# TanveerMPPT_02_1.net
KiCad netlist of a schematic drawn in EAGLE
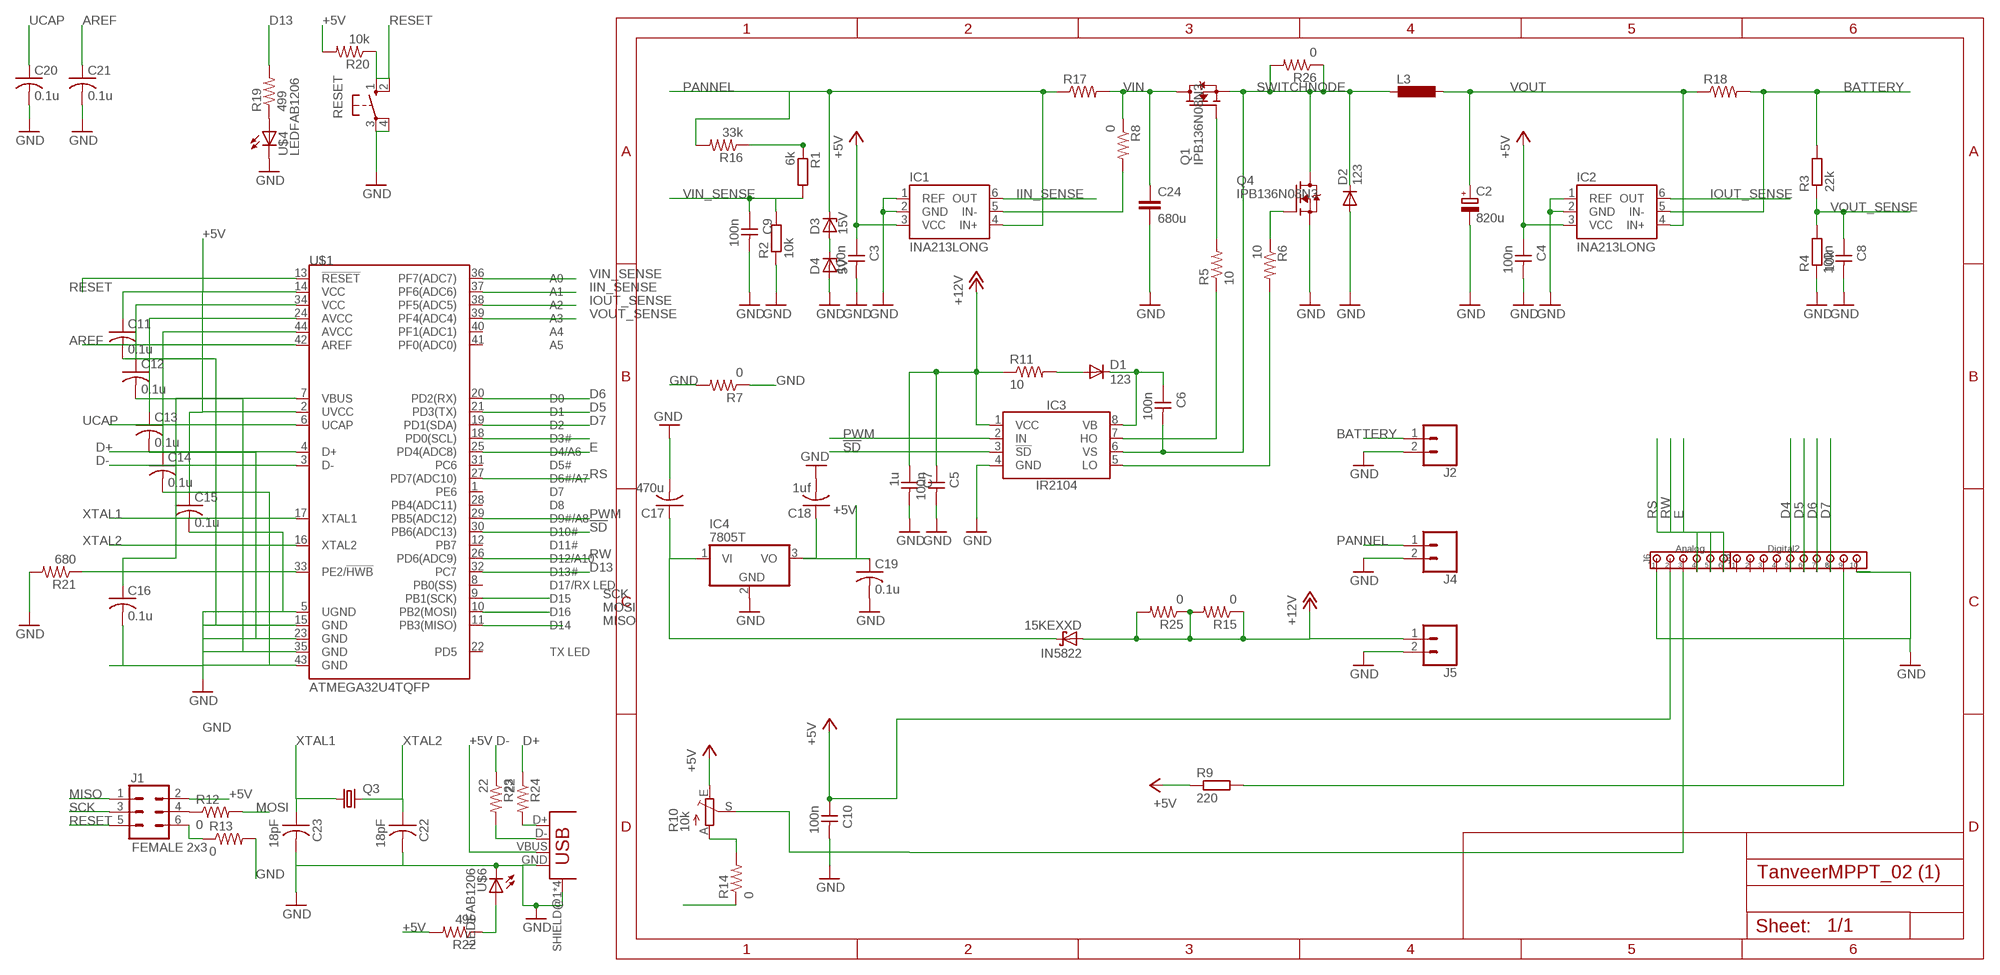
[diagram p0: schematic, sheet 1]

(export (version "E")
  (design (tool "Eeschema 10.0.6"))
  (components
    (comp (ref "C2")
      (value "820u")
      (footprint "eagle-import:10MM")
      (libsource (lib "eagle-import") (part "C_POLARIZED10MM"))
    )
    (comp (ref "C3")
      (value "100n")
      (footprint "eagle-import:C1206")
      (libsource (lib "eagle-import") (part "CAP-UNPOLARIZED"))
    )
    (comp (ref "C4")
      (value "100n")
      (footprint "eagle-import:C1206FAB")
      (libsource (lib "eagle-import") (part "CAP-UNPOLARIZEDFAB"))
    )
    (comp (ref "C5")
      (value "100n")
      (footprint "eagle-import:C1206FAB")
      (libsource (lib "eagle-import") (part "CAP-UNPOLARIZEDFAB"))
    )
    (comp (ref "C6")
      (value "100n")
      (footprint "eagle-import:C1206FAB")
      (libsource (lib "eagle-import") (part "CAP-UNPOLARIZEDFAB"))
    )
    (comp (ref "C7")
      (value "1u")
      (footprint "eagle-import:C1206FAB")
      (libsource (lib "eagle-import") (part "CAP-UNPOLARIZEDFAB"))
    )
    (comp (ref "C8")
      (value "100n")
      (footprint "eagle-import:C1206")
      (libsource (lib "eagle-import") (part "CAP-UNPOLARIZED"))
    )
    (comp (ref "C9")
      (value "100n")
      (footprint "eagle-import:C1206FAB")
      (libsource (lib "eagle-import") (part "CAP-UNPOLARIZEDFAB"))
    )
    (comp (ref "C10")
      (value "100n")
      (footprint "eagle-import:C1206FAB")
      (libsource (lib "eagle-import") (part "CAP-UNPOLARIZEDFAB"))
    )
    (comp (ref "C11")
      (value "0.1u")
      (footprint "eagle-import:C1206")
      (libsource (lib "eagle-import") (part "C-USC1206"))
    )
    (comp (ref "C12")
      (value "0.1u")
      (footprint "eagle-import:C1206")
      (libsource (lib "eagle-import") (part "C-USC1206"))
    )
    (comp (ref "C13")
      (value "0.1u")
      (footprint "eagle-import:C1206")
      (libsource (lib "eagle-import") (part "C-USC1206"))
    )
    (comp (ref "C14")
      (value "0.1u")
      (footprint "eagle-import:C1206")
      (libsource (lib "eagle-import") (part "C-USC1206"))
    )
    (comp (ref "C15")
      (value "0.1u")
      (footprint "eagle-import:C1206")
      (libsource (lib "eagle-import") (part "C-USC1206"))
    )
    (comp (ref "C16")
      (value "0.1u")
      (footprint "eagle-import:C1206")
      (libsource (lib "eagle-import") (part "C-USC1206"))
    )
    (comp (ref "C17")
      (value "470u")
      (footprint "eagle-import:C1206")
      (libsource (lib "eagle-import") (part "C-USC1206"))
    )
    (comp (ref "C18")
      (value "1uf")
      (footprint "eagle-import:C1206")
      (libsource (lib "eagle-import") (part "C-USC1206"))
    )
    (comp (ref "C19")
      (value "0.1u")
      (footprint "eagle-import:C1206")
      (libsource (lib "eagle-import") (part "C-USC1206"))
    )
    (comp (ref "C20")
      (value "0.1u")
      (footprint "eagle-import:C1206")
      (libsource (lib "eagle-import") (part "C-USC1206"))
    )
    (comp (ref "C21")
      (value "0.1u")
      (footprint "eagle-import:C1206")
      (libsource (lib "eagle-import") (part "C-USC1206"))
    )
    (comp (ref "C22")
      (value "18pF")
      (footprint "eagle-import:C1206FAB")
      (libsource (lib "eagle-import") (part "CAP-US1206FAB"))
    )
    (comp (ref "C23")
      (value "18pF")
      (footprint "eagle-import:C1206FAB")
      (libsource (lib "eagle-import") (part "CAP-US1206FAB"))
    )
    (comp (ref "C24")
      (value "680u")
      (footprint "eagle-import:CAP-PTH-10MM")
      (libsource (lib "eagle-import") (part "10NF-PTH-10MM-10000V-1-%"))
    )
    (comp (ref "D1")
      (value "123")
      (footprint "eagle-import:DO41-10")
      (libsource (lib "eagle-import") (part "1N4004"))
    )
    (comp (ref "D2")
      (value "123")
      (footprint "eagle-import:DO41-10")
      (libsource (lib "eagle-import") (part "1N4004"))
    )
    (comp (ref "D3")
      (value "15V")
      (footprint "eagle-import:DO41Z10")
      (libsource (lib "eagle-import") (part "ZENER-DIODEDO41Z10"))
    )
    (comp (ref "D4")
      (value "5V")
      (footprint "eagle-import:DO41Z10")
      (libsource (lib "eagle-import") (part "ZENER-DIODEDO41Z10"))
    )
    (comp (ref "IC1")
      (value "INA213LONG")
      (footprint "eagle-import:SC70-6_LONG")
      (libsource (lib "eagle-import") (part "INA21LONG3"))
    )
    (comp (ref "IC2")
      (value "INA213LONG")
      (footprint "eagle-import:SC70-6_LONG")
      (libsource (lib "eagle-import") (part "INA21LONG3"))
    )
    (comp (ref "IC3")
      (value "IR2104")
      (footprint "eagle-import:SOIC8")
      (libsource (lib "eagle-import") (part "IR2104"))
    )
    (comp (ref "IC4")
      (value "7805T")
      (footprint "eagle-import:TO220H")
      (libsource (lib "eagle-import") (part "78T05"))
    )
    (comp (ref "IN5822")
      (value "15KEXXD")
      (footprint "eagle-import:DO201T15")
      (libsource (lib "eagle-import") (part "15KEXXD"))
    )
    (comp (ref "J1")
      (value "FEMALE 2x3")
      (footprint "eagle-import:2X3")
      (libsource (lib "eagle-import") (part "CONN_03X2FEMALE"))
    )
    (comp (ref "J2")
      (value "CONN_02PTH4")
      (footprint "eagle-import:1X02_XTRA_BIG")
      (libsource (lib "eagle-import") (part "CONN_02PTH4"))
    )
    (comp (ref "J3")
      (value "Digital2")
      (footprint "eagle-import:100MIL_10X_ROUND")
      (libsource (lib "eagle-import") (part "100MIL_10X"))
    )
    (comp (ref "J4")
      (value "CONN_02PTH4")
      (footprint "eagle-import:1X02_XTRA_BIG")
      (libsource (lib "eagle-import") (part "CONN_02PTH4"))
    )
    (comp (ref "J5")
      (value "CONN_02PTH4")
      (footprint "eagle-import:1X02_XTRA_BIG")
      (libsource (lib "eagle-import") (part "CONN_02PTH4"))
    )
    (comp (ref "J6")
      (value "Analog")
      (footprint "eagle-import:100MIL_6X_ROUND")
      (libsource (lib "eagle-import") (part "100MIL_6X"))
    )
    (comp (ref "L3")
      (value "L-EUIR-4")
      (footprint "eagle-import:IR-4")
      (libsource (lib "eagle-import") (part "L-EUIR-4"))
    )
    (comp (ref "Q1")
      (value "IPB136N08N3")
      (footprint "eagle-import:TO263-3")
      (libsource (lib "eagle-import") (part "N-PWR-MOSFETTO263-3"))
    )
    (comp (ref "Q3")
      (value "CRYSTALTC26V")
      (footprint "eagle-import:TC26V")
      (libsource (lib "eagle-import") (part "CRYSTALTC26V"))
    )
    (comp (ref "Q4")
      (value "IPB136N08N3")
      (footprint "eagle-import:TO263-3")
      (libsource (lib "eagle-import") (part "N-PWR-MOSFETTO263-3"))
    )
    (comp (ref "R1")
      (value "6k")
      (footprint "eagle-import:M1206")
      (libsource (lib "eagle-import") (part "R-EU_M1206"))
    )
    (comp (ref "R2")
      (value "10k")
      (footprint "eagle-import:M1206")
      (libsource (lib "eagle-import") (part "R-EU_M1206"))
    )
    (comp (ref "R3")
      (value "22k")
      (footprint "eagle-import:M1206")
      (libsource (lib "eagle-import") (part "R-EU_M1206"))
    )
    (comp (ref "R4")
      (value "10k")
      (footprint "eagle-import:M1206")
      (libsource (lib "eagle-import") (part "R-EU_M1206"))
    )
    (comp (ref "R5")
      (value "10")
      (footprint "eagle-import:R1206FAB")
      (libsource (lib "eagle-import") (part "RES-US1206FAB"))
    )
    (comp (ref "R6")
      (value "10")
      (footprint "eagle-import:R1206FAB")
      (libsource (lib "eagle-import") (part "RES-US1206FAB"))
    )
    (comp (ref "R7")
      (value "0")
      (footprint "eagle-import:R1206FAB")
      (libsource (lib "eagle-import") (part "RES-US1206FAB"))
    )
    (comp (ref "R8")
      (value "0")
      (footprint "eagle-import:R1206FAB")
      (libsource (lib "eagle-import") (part "RES-US1206FAB"))
    )
    (comp (ref "R9")
      (value "220")
      (footprint "eagle-import:M1206")
      (libsource (lib "eagle-import") (part "R-EU_M1206"))
    )
    (comp (ref "R10")
      (value "10k")
      (footprint "eagle-import:B25X")
      (libsource (lib "eagle-import") (part "TRIM_EU-B25X"))
    )
    (comp (ref "R11")
      (value "10")
      (footprint "eagle-import:R1206FAB")
      (libsource (lib "eagle-import") (part "RES-US1206FAB"))
    )
    (comp (ref "R12")
      (value "0")
      (footprint "eagle-import:R1206FAB")
      (libsource (lib "eagle-import") (part "RES-US1206FAB"))
    )
    (comp (ref "R13")
      (value "0")
      (footprint "eagle-import:R1206FAB")
      (libsource (lib "eagle-import") (part "RES-US1206FAB"))
    )
    (comp (ref "R14")
      (value "0")
      (footprint "eagle-import:R1206FAB")
      (libsource (lib "eagle-import") (part "RES-US1206FAB"))
    )
    (comp (ref "R15")
      (value "0")
      (footprint "eagle-import:R1206FAB")
      (libsource (lib "eagle-import") (part "RES-US1206FAB"))
    )
    (comp (ref "R16")
      (value "33k")
      (footprint "eagle-import:R1206FAB")
      (libsource (lib "eagle-import") (part "RES-US1206FAB"))
    )
    (comp (ref "R17")
      (value "R-US_R2512")
      (footprint "eagle-import:R2512")
      (libsource (lib "eagle-import") (part "R-US_R2512"))
    )
    (comp (ref "R18")
      (value "R-US_R2512")
      (footprint "eagle-import:R2512")
      (libsource (lib "eagle-import") (part "R-US_R2512"))
    )
    (comp (ref "R19")
      (value "499")
      (footprint "eagle-import:R1206FAB")
      (libsource (lib "eagle-import") (part "RES-US1206FAB"))
    )
    (comp (ref "R20")
      (value "10k")
      (footprint "eagle-import:R1206")
      (libsource (lib "eagle-import") (part "RES-US1206"))
    )
    (comp (ref "R21")
      (value "680")
      (footprint "eagle-import:R1206FAB")
      (libsource (lib "eagle-import") (part "RES-US1206FAB"))
    )
    (comp (ref "R22")
      (value "499")
      (footprint "eagle-import:R1206")
      (libsource (lib "eagle-import") (part "RES-US1206"))
    )
    (comp (ref "R23")
      (value "22")
      (footprint "eagle-import:R1206")
      (libsource (lib "eagle-import") (part "RES-US1206"))
    )
    (comp (ref "R24")
      (value "22")
      (footprint "eagle-import:R1206")
      (libsource (lib "eagle-import") (part "RES-US1206"))
    )
    (comp (ref "R25")
      (value "0")
      (footprint "eagle-import:R1206FAB")
      (libsource (lib "eagle-import") (part "RES-US1206FAB"))
    )
    (comp (ref "R26")
      (value "0")
      (footprint "eagle-import:R1206FAB")
      (libsource (lib "eagle-import") (part "RES-US1206FAB"))
    )
    (comp (ref "RESET")
      (value "10-XX")
      (footprint "eagle-import:B3F-10XX")
      (fields (field (name "MPN") "B3F-1000"))
      (libsource (lib "eagle-import") (part "10-XX"))
    )
    (comp (ref "U$1")
      (value "ATMEGA32U4TQFP")
      (footprint "eagle-import:SPARKFUN-DIGITALIC_TQFP44")
      (libsource (lib "eagle-import") (part "ATMEGA32U4TQFP"))
    )
    (comp (ref "U$4")
      (value "LEDFAB1206")
      (footprint "eagle-import:LED1206FAB")
      (libsource (lib "eagle-import") (part "LEDFAB1206"))
    )
    (comp (ref "U$5")
      (value "USB_MINIB")
      (footprint "eagle-import:USB_MINIB")
      (libsource (lib "eagle-import") (part "USB_MINIB"))
    )
    (comp (ref "U$6")
      (value "LEDFAB1206")
      (footprint "eagle-import:LED1206FAB")
      (libsource (lib "eagle-import") (part "LEDFAB1206"))
    )
  )
  (nets
    (net (code "1") (name "+5V") (class "Default")
      (node (ref "C10") (pin "1") (pinfunction "1_1") (pintype "passive"))
      (node (ref "C11") (pin "1") (pinfunction "1_1") (pintype "passive"))
      (node (ref "C12") (pin "1") (pinfunction "1_1") (pintype "passive"))
      (node (ref "C13") (pin "1") (pinfunction "1_1") (pintype "passive"))
      (node (ref "C14") (pin "1") (pinfunction "1_1") (pintype "passive"))
      (node (ref "C15") (pin "1") (pinfunction "1_1") (pintype "passive"))
      (node (ref "C16") (pin "1") (pinfunction "1_1") (pintype "passive"))
      (node (ref "C18") (pin "1") (pinfunction "1_1") (pintype "passive"))
      (node (ref "C19") (pin "1") (pinfunction "1_1") (pintype "passive"))
      (node (ref "C3") (pin "1") (pinfunction "1_1") (pintype "passive"))
      (node (ref "C4") (pin "1") (pinfunction "1_1") (pintype "passive"))
      (node (ref "IC1") (pin "3") (pinfunction "VCC_3") (pintype "passive"))
      (node (ref "IC2") (pin "3") (pinfunction "VCC_3") (pintype "passive"))
      (node (ref "IC4") (pin "3") (pinfunction "VO_3") (pintype "passive"))
      (node (ref "J1") (pin "2") (pinfunction "2_2") (pintype "bidirectional"))
      (node (ref "J6") (pin "2") (pinfunction "2_2") (pintype "passive"))
      (node (ref "R10") (pin "E") (pinfunction "E_E") (pintype "passive"))
      (node (ref "R20") (pin "2") (pinfunction "2_2") (pintype "passive"))
      (node (ref "R22") (pin "2") (pinfunction "2_2") (pintype "passive"))
      (node (ref "R9") (pin "1") (pinfunction "1_1") (pintype "passive"))
      (node (ref "U$1") (pin "14") (pinfunction "VCC_14") (pintype "bidirectional"))
      (node (ref "U$1") (pin "2") (pinfunction "UVCC_2") (pintype "bidirectional"))
      (node (ref "U$1") (pin "24") (pinfunction "AVCC_24") (pintype "bidirectional"))
      (node (ref "U$1") (pin "34") (pinfunction "VCC_34") (pintype "bidirectional"))
      (node (ref "U$1") (pin "44") (pinfunction "AVCC_44") (pintype "bidirectional"))
      (node (ref "U$1") (pin "7") (pinfunction "VBUS_7") (pintype "bidirectional"))
      (node (ref "U$5") (pin "VBUS") (pinfunction "VBUS_VBUS") (pintype "bidirectional"))
    )
    (net (code "2") (name "+12V") (class "Default")
      (node (ref "C5") (pin "1") (pinfunction "1_1") (pintype "passive"))
      (node (ref "C7") (pin "1") (pinfunction "1_1") (pintype "passive"))
      (node (ref "IC3") (pin "1") (pinfunction "VCC_1") (pintype "input"))
      (node (ref "IN5822") (pin "A") (pinfunction "A_A") (pintype "passive"))
      (node (ref "J5") (pin "1") (pinfunction "1_1") (pintype "passive"))
      (node (ref "R11") (pin "1") (pinfunction "1_1") (pintype "passive"))
      (node (ref "R15") (pin "1") (pinfunction "1_1") (pintype "passive"))
      (node (ref "R15") (pin "2") (pinfunction "2_2") (pintype "passive"))
      (node (ref "R25") (pin "1") (pinfunction "1_1") (pintype "passive"))
      (node (ref "R25") (pin "2") (pinfunction "2_2") (pintype "passive"))
    )
    (net (code "3") (name "/AREF") (class "Default")
      (node (ref "C21") (pin "1") (pinfunction "1_1") (pintype "passive"))
      (node (ref "U$1") (pin "42") (pinfunction "AREF_42") (pintype "bidirectional"))
    )
    (net (code "4") (name "/BATTERY") (class "Default")
      (node (ref "IC2") (pin "5") (pinfunction "IN-_5") (pintype "output"))
      (node (ref "J2") (pin "1") (pinfunction "1_1") (pintype "passive"))
      (node (ref "R18") (pin "2") (pinfunction "2_2") (pintype "passive"))
      (node (ref "R3") (pin "2") (pinfunction "2_2") (pintype "passive"))
    )
    (net (code "5") (name "/D+") (class "Default")
      (node (ref "R24") (pin "1") (pinfunction "1_1") (pintype "passive"))
      (node (ref "U$1") (pin "4") (pinfunction "D+_4") (pintype "bidirectional"))
    )
    (net (code "6") (name "/D-") (class "Default")
      (node (ref "R23") (pin "1") (pinfunction "1_1") (pintype "passive"))
      (node (ref "U$1") (pin "3") (pinfunction "D-_3") (pintype "bidirectional"))
    )
    (net (code "7") (name "/D4") (class "Default")
      (node (ref "J3") (pin "5") (pinfunction "P$5_5") (pintype "passive"))
      (node (ref "U$1") (pin "18") (pinfunction "PD0(SCL)_18") (pintype "bidirectional"))
    )
    (net (code "8") (name "/D5") (class "Default")
      (node (ref "J3") (pin "6") (pinfunction "P$6_6") (pintype "passive"))
      (node (ref "U$1") (pin "21") (pinfunction "PD3(TX)_21") (pintype "bidirectional"))
    )
    (net (code "9") (name "/D6") (class "Default")
      (node (ref "J3") (pin "7") (pinfunction "P$7_7") (pintype "passive"))
      (node (ref "U$1") (pin "20") (pinfunction "PD2(RX)_20") (pintype "bidirectional"))
    )
    (net (code "10") (name "/D7") (class "Default")
      (node (ref "J3") (pin "8") (pinfunction "P$8_8") (pintype "passive"))
      (node (ref "U$1") (pin "19") (pinfunction "PD1(SDA)_19") (pintype "bidirectional"))
    )
    (net (code "11") (name "/D13") (class "Default")
      (node (ref "R19") (pin "2") (pinfunction "2_2") (pintype "passive"))
      (node (ref "U$1") (pin "32") (pinfunction "PC7_32") (pintype "bidirectional"))
    )
    (net (code "12") (name "/E") (class "Default")
      (node (ref "J6") (pin "6") (pinfunction "6_6") (pintype "passive"))
      (node (ref "U$1") (pin "25") (pinfunction "PD4(ADC8)_25") (pintype "bidirectional"))
    )
    (net (code "13") (name "/IIN_SENSE") (class "Default")
      (node (ref "IC1") (pin "6") (pinfunction "OUT_6") (pintype "output"))
      (node (ref "U$1") (pin "37") (pinfunction "PF6(ADC6)_37") (pintype "bidirectional"))
    )
    (net (code "14") (name "/IOUT_SENSE") (class "Default")
      (node (ref "IC2") (pin "6") (pinfunction "OUT_6") (pintype "output"))
      (node (ref "U$1") (pin "38") (pinfunction "PF5(ADC5)_38") (pintype "bidirectional"))
    )
    (net (code "15") (name "/MISO") (class "Default")
      (node (ref "J1") (pin "1") (pinfunction "1_1") (pintype "bidirectional"))
      (node (ref "U$1") (pin "11") (pinfunction "PB3(MISO)_11") (pintype "bidirectional"))
    )
    (net (code "16") (name "/MOSI") (class "Default")
      (node (ref "R12") (pin "2") (pinfunction "2_2") (pintype "passive"))
      (node (ref "U$1") (pin "10") (pinfunction "PB2(MOSI)_10") (pintype "bidirectional"))
    )
    (net (code "17") (name "/PANNEL") (class "Default")
      (node (ref "D3") (pin "C") (pinfunction "C_C") (pintype "passive"))
      (node (ref "IC1") (pin "4") (pinfunction "IN+_4") (pintype "output"))
      (node (ref "J4") (pin "1") (pinfunction "1_1") (pintype "passive"))
      (node (ref "R16") (pin "2") (pinfunction "2_2") (pintype "passive"))
      (node (ref "R17") (pin "1") (pinfunction "1_1") (pintype "passive"))
    )
    (net (code "18") (name "/PWM") (class "Default")
      (node (ref "IC3") (pin "2") (pinfunction "IN_2") (pintype "input"))
      (node (ref "U$1") (pin "29") (pinfunction "PB5(ADC12)_29") (pintype "bidirectional"))
    )
    (net (code "19") (name "/RESET") (class "Default")
      (node (ref "J1") (pin "5") (pinfunction "5_5") (pintype "bidirectional"))
      (node (ref "R20") (pin "1") (pinfunction "1_1") (pintype "passive"))
      (node (ref "RESET") (pin "1") (pinfunction "S_1") (pintype "passive"))
      (node (ref "RESET") (pin "2") (pinfunction "S1_2") (pintype "passive"))
      (node (ref "U$1") (pin "13") (pinfunction "~{RESET}_13") (pintype "bidirectional"))
    )
    (net (code "20") (name "/RS") (class "Default")
      (node (ref "J6") (pin "4") (pinfunction "4_4") (pintype "passive"))
      (node (ref "U$1") (pin "27") (pinfunction "PD7(ADC10)_27") (pintype "bidirectional"))
    )
    (net (code "21") (name "/RW") (class "Default")
      (node (ref "J6") (pin "5") (pinfunction "5_5") (pintype "passive"))
      (node (ref "U$1") (pin "26") (pinfunction "PD6(ADC9)_26") (pintype "bidirectional"))
    )
    (net (code "22") (name "/SCK") (class "Default")
      (node (ref "J1") (pin "3") (pinfunction "3_3") (pintype "bidirectional"))
      (node (ref "U$1") (pin "9") (pinfunction "PB1(SCK)_9") (pintype "bidirectional"))
    )
    (net (code "23") (name "/SWITCHNODE") (class "Default")
      (node (ref "C6") (pin "2") (pinfunction "2_2") (pintype "passive"))
      (node (ref "D2") (pin "C") (pinfunction "C_C") (pintype "passive"))
      (node (ref "IC3") (pin "6") (pinfunction "VS_6") (pintype "bidirectional"))
      (node (ref "L3") (pin "2") (pinfunction "2_2") (pintype "passive"))
      (node (ref "Q1") (pin "3") (pinfunction "S_3") (pintype "passive"))
      (node (ref "Q4") (pin "TAB") (pinfunction "D_TAB") (pintype "passive"))
      (node (ref "R26") (pin "1") (pinfunction "1_1") (pintype "passive"))
      (node (ref "R26") (pin "2") (pinfunction "2_2") (pintype "passive"))
    )
    (net (code "24") (name "/UCAP") (class "Default")
      (node (ref "C20") (pin "1") (pinfunction "1_1") (pintype "passive"))
      (node (ref "U$1") (pin "6") (pinfunction "UCAP_6") (pintype "bidirectional"))
    )
    (net (code "25") (name "/VIN") (class "Default")
      (node (ref "C24") (pin "1") (pinfunction "1_1") (pintype "passive"))
      (node (ref "Q1") (pin "TAB") (pinfunction "D_TAB") (pintype "passive"))
      (node (ref "R17") (pin "2") (pinfunction "2_2") (pintype "passive"))
      (node (ref "R8") (pin "1") (pinfunction "1_1") (pintype "passive"))
    )
    (net (code "26") (name "/VIN_SENSE") (class "Default")
      (node (ref "C9") (pin "1") (pinfunction "1_1") (pintype "passive"))
      (node (ref "R1") (pin "2") (pinfunction "2_2") (pintype "passive"))
      (node (ref "R2") (pin "2") (pinfunction "2_2") (pintype "passive"))
      (node (ref "U$1") (pin "36") (pinfunction "PF7(ADC7)_36") (pintype "bidirectional"))
    )
    (net (code "27") (name "/VOUT") (class "Default")
      (node (ref "C2") (pin "+") (pinfunction "+_+") (pintype "passive"))
      (node (ref "IC2") (pin "4") (pinfunction "IN+_4") (pintype "output"))
      (node (ref "L3") (pin "1") (pinfunction "1_1") (pintype "passive"))
      (node (ref "R18") (pin "1") (pinfunction "1_1") (pintype "passive"))
    )
    (net (code "28") (name "/VOUT_SENSE") (class "Default")
      (node (ref "C8") (pin "1") (pinfunction "1_1") (pintype "passive"))
      (node (ref "R3") (pin "1") (pinfunction "1_1") (pintype "passive"))
      (node (ref "R4") (pin "2") (pinfunction "2_2") (pintype "passive"))
      (node (ref "U$1") (pin "39") (pinfunction "PF4(ADC4)_39") (pintype "bidirectional"))
    )
    (net (code "29") (name "/XTAL1") (class "Default")
      (node (ref "C23") (pin "1") (pinfunction "1_1") (pintype "passive"))
      (node (ref "Q3") (pin "1") (pinfunction "1_1") (pintype "passive"))
      (node (ref "U$1") (pin "17") (pinfunction "XTAL1_17") (pintype "bidirectional"))
    )
    (net (code "30") (name "/XTAL2") (class "Default")
      (node (ref "C22") (pin "1") (pinfunction "1_1") (pintype "passive"))
      (node (ref "Q3") (pin "2") (pinfunction "2_2") (pintype "passive"))
      (node (ref "U$1") (pin "16") (pinfunction "XTAL2_16") (pintype "bidirectional"))
    )
    (net (code "31") (name "/~{SD}") (class "Default")
      (node (ref "IC3") (pin "3") (pinfunction "~{SD}_3") (pintype "input"))
      (node (ref "U$1") (pin "30") (pinfunction "PB6(ADC13)_30") (pintype "bidirectional"))
    )
    (net (code "32") (name "GND") (class "Default")
      (node (ref "C10") (pin "2") (pinfunction "2_2") (pintype "passive"))
      (node (ref "C11") (pin "2") (pinfunction "2_2") (pintype "passive"))
      (node (ref "C12") (pin "2") (pinfunction "2_2") (pintype "passive"))
      (node (ref "C13") (pin "2") (pinfunction "2_2") (pintype "passive"))
      (node (ref "C14") (pin "2") (pinfunction "2_2") (pintype "passive"))
      (node (ref "C15") (pin "2") (pinfunction "2_2") (pintype "passive"))
      (node (ref "C16") (pin "2") (pinfunction "2_2") (pintype "passive"))
      (node (ref "C17") (pin "2") (pinfunction "2_2") (pintype "passive"))
      (node (ref "C18") (pin "2") (pinfunction "2_2") (pintype "passive"))
      (node (ref "C19") (pin "2") (pinfunction "2_2") (pintype "passive"))
      (node (ref "C2") (pin "-") (pinfunction "-_-") (pintype "passive"))
      (node (ref "C20") (pin "2") (pinfunction "2_2") (pintype "passive"))
      (node (ref "C21") (pin "2") (pinfunction "2_2") (pintype "passive"))
      (node (ref "C22") (pin "2") (pinfunction "2_2") (pintype "passive"))
      (node (ref "C23") (pin "2") (pinfunction "2_2") (pintype "passive"))
      (node (ref "C24") (pin "2") (pinfunction "2_2") (pintype "passive"))
      (node (ref "C3") (pin "2") (pinfunction "2_2") (pintype "passive"))
      (node (ref "C4") (pin "2") (pinfunction "2_2") (pintype "passive"))
      (node (ref "C5") (pin "2") (pinfunction "2_2") (pintype "passive"))
      (node (ref "C7") (pin "2") (pinfunction "2_2") (pintype "passive"))
      (node (ref "C8") (pin "2") (pinfunction "2_2") (pintype "passive"))
      (node (ref "C9") (pin "2") (pinfunction "2_2") (pintype "passive"))
      (node (ref "D2") (pin "A") (pinfunction "A_A") (pintype "passive"))
      (node (ref "D4") (pin "A") (pinfunction "A_A") (pintype "passive"))
      (node (ref "IC1") (pin "1") (pinfunction "REF_1") (pintype "passive"))
      (node (ref "IC1") (pin "2") (pinfunction "GND_2") (pintype "passive"))
      (node (ref "IC2") (pin "1") (pinfunction "REF_1") (pintype "passive"))
      (node (ref "IC2") (pin "2") (pinfunction "GND_2") (pintype "passive"))
      (node (ref "IC3") (pin "4") (pinfunction "GND_4") (pintype "input"))
      (node (ref "IC4") (pin "2") (pinfunction "GND_2") (pintype "passive"))
      (node (ref "J2") (pin "2") (pinfunction "2_2") (pintype "passive"))
      (node (ref "J3") (pin "10") (pinfunction "P$10_10") (pintype "passive"))
      (node (ref "J4") (pin "2") (pinfunction "2_2") (pintype "passive"))
      (node (ref "J5") (pin "2") (pinfunction "2_2") (pintype "passive"))
      (node (ref "J6") (pin "1") (pinfunction "1_1") (pintype "passive"))
      (node (ref "Q4") (pin "3") (pinfunction "S_3") (pintype "passive"))
      (node (ref "R10") (pin "A") (pinfunction "A_A") (pintype "passive"))
      (node (ref "R13") (pin "2") (pinfunction "2_2") (pintype "passive"))
      (node (ref "R14") (pin "1") (pinfunction "1_1") (pintype "passive"))
      (node (ref "R14") (pin "2") (pinfunction "2_2") (pintype "passive"))
      (node (ref "R2") (pin "1") (pinfunction "1_1") (pintype "passive"))
      (node (ref "R21") (pin "2") (pinfunction "2_2") (pintype "passive"))
      (node (ref "R4") (pin "1") (pinfunction "1_1") (pintype "passive"))
      (node (ref "R7") (pin "1") (pinfunction "1_1") (pintype "passive"))
      (node (ref "R7") (pin "2") (pinfunction "2_2") (pintype "passive"))
      (node (ref "RESET") (pin "3") (pinfunction "P_3") (pintype "passive"))
      (node (ref "RESET") (pin "4") (pinfunction "P1_4") (pintype "passive"))
      (node (ref "U$1") (pin "15") (pinfunction "GND_15") (pintype "bidirectional"))
      (node (ref "U$1") (pin "23") (pinfunction "GND_23") (pintype "bidirectional"))
      (node (ref "U$1") (pin "35") (pinfunction "GND_35") (pintype "bidirectional"))
      (node (ref "U$1") (pin "43") (pinfunction "GND_43") (pintype "bidirectional"))
      (node (ref "U$1") (pin "5") (pinfunction "UGND_5") (pintype "bidirectional"))
      (node (ref "U$4") (pin "2") (pinfunction "C_2") (pintype "passive"))
      (node (ref "U$5") (pin "GND") (pinfunction "GND_GND") (pintype "bidirectional"))
      (node (ref "U$5") (pin "SHIELD@1") (pinfunction "SHIELD_SHIELD@1") (pintype "passive"))
      (node (ref "U$5") (pin "SHIELD@2") (pinfunction "SHIELD_SHIELD@2") (pintype "passive"))
      (node (ref "U$5") (pin "SHIELD@3") (pinfunction "SHIELD_SHIELD@3") (pintype "passive"))
      (node (ref "U$5") (pin "SHIELD@4") (pinfunction "SHIELD_SHIELD@4") (pintype "passive"))
      (node (ref "U$6") (pin "2") (pinfunction "C_2") (pintype "passive"))
    )
    (net (code "33") (name "Net-(D1-PadA)") (class "Default")
      (node (ref "D1") (pin "A") (pinfunction "A_A") (pintype "passive"))
      (node (ref "R11") (pin "2") (pinfunction "2_2") (pintype "passive"))
    )
    (net (code "34") (name "Net-(D3-PadA)") (class "Default")
      (node (ref "D3") (pin "A") (pinfunction "A_A") (pintype "passive"))
      (node (ref "D4") (pin "C") (pinfunction "C_C") (pintype "passive"))
    )
    (net (code "35") (name "Net-(IC1-IN-)") (class "Default")
      (node (ref "IC1") (pin "5") (pinfunction "IN-_5") (pintype "output"))
      (node (ref "R8") (pin "2") (pinfunction "2_2") (pintype "passive"))
    )
    (net (code "36") (name "Net-(IC3-HO)") (class "Default")
      (node (ref "IC3") (pin "7") (pinfunction "HO_7") (pintype "bidirectional"))
      (node (ref "R5") (pin "1") (pinfunction "1_1") (pintype "passive"))
    )
    (net (code "37") (name "Net-(IC3-LO)") (class "Default")
      (node (ref "IC3") (pin "5") (pinfunction "LO_5") (pintype "bidirectional"))
      (node (ref "R6") (pin "2") (pinfunction "2_2") (pintype "passive"))
    )
    (net (code "38") (name "Net-(IC3-VB)") (class "Default")
      (node (ref "C6") (pin "1") (pinfunction "1_1") (pintype "passive"))
      (node (ref "D1") (pin "C") (pinfunction "C_C") (pintype "passive"))
      (node (ref "IC3") (pin "8") (pinfunction "VB_8") (pintype "power_in"))
    )
    (net (code "39") (name "Net-(IC4-VI)") (class "Default")
      (node (ref "C17") (pin "1") (pinfunction "1_1") (pintype "passive"))
      (node (ref "IC4") (pin "1") (pinfunction "VI_1") (pintype "input"))
      (node (ref "IN5822") (pin "C") (pinfunction "C_C") (pintype "passive"))
    )
    (net (code "40") (name "Net-(J1-Pad4)") (class "Default")
      (node (ref "J1") (pin "4") (pinfunction "4_4") (pintype "bidirectional"))
      (node (ref "R12") (pin "1") (pinfunction "1_1") (pintype "passive"))
    )
    (net (code "41") (name "Net-(J1-Pad6)") (class "Default")
      (node (ref "J1") (pin "6") (pinfunction "6_6") (pintype "bidirectional"))
      (node (ref "R13") (pin "1") (pinfunction "1_1") (pintype "passive"))
    )
    (net (code "42") (name "Net-(J3-P$9)") (class "Default")
      (node (ref "J3") (pin "9") (pinfunction "P$9_9") (pintype "passive"))
      (node (ref "R9") (pin "2") (pinfunction "2_2") (pintype "passive"))
    )
    (net (code "43") (name "Net-(J6-Pad3)") (class "Default")
      (node (ref "J6") (pin "3") (pinfunction "3_3") (pintype "passive"))
      (node (ref "R10") (pin "S") (pinfunction "S_S") (pintype "passive"))
    )
    (net (code "44") (name "Net-(Q1-G)") (class "Default")
      (node (ref "Q1") (pin "1") (pinfunction "G_1") (pintype "passive"))
      (node (ref "R5") (pin "2") (pinfunction "2_2") (pintype "passive"))
    )
    (net (code "45") (name "Net-(Q4-G)") (class "Default")
      (node (ref "Q4") (pin "1") (pinfunction "G_1") (pintype "passive"))
      (node (ref "R6") (pin "1") (pinfunction "1_1") (pintype "passive"))
    )
    (net (code "46") (name "Net-(R1-Pad1)") (class "Default")
      (node (ref "R1") (pin "1") (pinfunction "1_1") (pintype "passive"))
      (node (ref "R16") (pin "1") (pinfunction "1_1") (pintype "passive"))
    )
    (net (code "47") (name "Net-(R23-Pad2)") (class "Default")
      (node (ref "R23") (pin "2") (pinfunction "2_2") (pintype "passive"))
      (node (ref "U$5") (pin "D-") (pinfunction "D-_D-") (pintype "bidirectional"))
    )
    (net (code "48") (name "Net-(R24-Pad2)") (class "Default")
      (node (ref "R24") (pin "2") (pinfunction "2_2") (pintype "passive"))
      (node (ref "U$5") (pin "D+") (pinfunction "D+_D+") (pintype "bidirectional"))
    )
    (net (code "49") (name "Net-(U$1-PE2{slash}~{HWB})") (class "Default")
      (node (ref "R21") (pin "1") (pinfunction "1_1") (pintype "passive"))
      (node (ref "U$1") (pin "33") (pinfunction "PE2/~{HWB}_33") (pintype "bidirectional"))
    )
    (net (code "50") (name "Net-(U$4-A)") (class "Default")
      (node (ref "R19") (pin "1") (pinfunction "1_1") (pintype "passive"))
      (node (ref "U$4") (pin "1") (pinfunction "A_1") (pintype "passive"))
    )
    (net (code "51") (name "Net-(U$6-A)") (class "Default")
      (node (ref "R22") (pin "1") (pinfunction "1_1") (pintype "passive"))
      (node (ref "U$6") (pin "1") (pinfunction "A_1") (pintype "passive"))
    )
    (net (code "52") (name "unconnected-(J3-P$1-Pad1)") (class "Default")
      (node (ref "J3") (pin "1") (pinfunction "P$1_1") (pintype "passive"))
    )
    (net (code "53") (name "unconnected-(J3-P$2-Pad2)") (class "Default")
      (node (ref "J3") (pin "2") (pinfunction "P$2_2") (pintype "passive"))
    )
    (net (code "54") (name "unconnected-(J3-P$3-Pad3)") (class "Default")
      (node (ref "J3") (pin "3") (pinfunction "P$3_3") (pintype "passive"))
    )
    (net (code "55") (name "unconnected-(J3-P$4-Pad4)") (class "Default")
      (node (ref "J3") (pin "4") (pinfunction "P$4_4") (pintype "passive"))
    )
    (net (code "56") (name "unconnected-(U$1-PB0(SS)-Pad8)") (class "Default")
      (node (ref "U$1") (pin "8") (pinfunction "PB0(SS)_8") (pintype "bidirectional"))
    )
    (net (code "57") (name "unconnected-(U$1-PB4(ADC11)-Pad28)") (class "Default")
      (node (ref "U$1") (pin "28") (pinfunction "PB4(ADC11)_28") (pintype "bidirectional"))
    )
    (net (code "58") (name "unconnected-(U$1-PB7-Pad12)") (class "Default")
      (node (ref "U$1") (pin "12") (pinfunction "PB7_12") (pintype "bidirectional"))
    )
    (net (code "59") (name "unconnected-(U$1-PC6-Pad31)") (class "Default")
      (node (ref "U$1") (pin "31") (pinfunction "PC6_31") (pintype "bidirectional"))
    )
    (net (code "60") (name "unconnected-(U$1-PD5-Pad22)") (class "Default")
      (node (ref "U$1") (pin "22") (pinfunction "PD5_22") (pintype "bidirectional"))
    )
    (net (code "61") (name "unconnected-(U$1-PE6-Pad1)") (class "Default")
      (node (ref "U$1") (pin "1") (pinfunction "PE6_1") (pintype "bidirectional"))
    )
    (net (code "62") (name "unconnected-(U$1-PF0(ADC0)-Pad41)") (class "Default")
      (node (ref "U$1") (pin "41") (pinfunction "PF0(ADC0)_41") (pintype "bidirectional"))
    )
    (net (code "63") (name "unconnected-(U$1-PF1(ADC1)-Pad40)") (class "Default")
      (node (ref "U$1") (pin "40") (pinfunction "PF1(ADC1)_40") (pintype "bidirectional"))
    )
  )
)
